# leaf_ard_rev_A.net
KiCad netlist of a schematic drawn in EAGLE
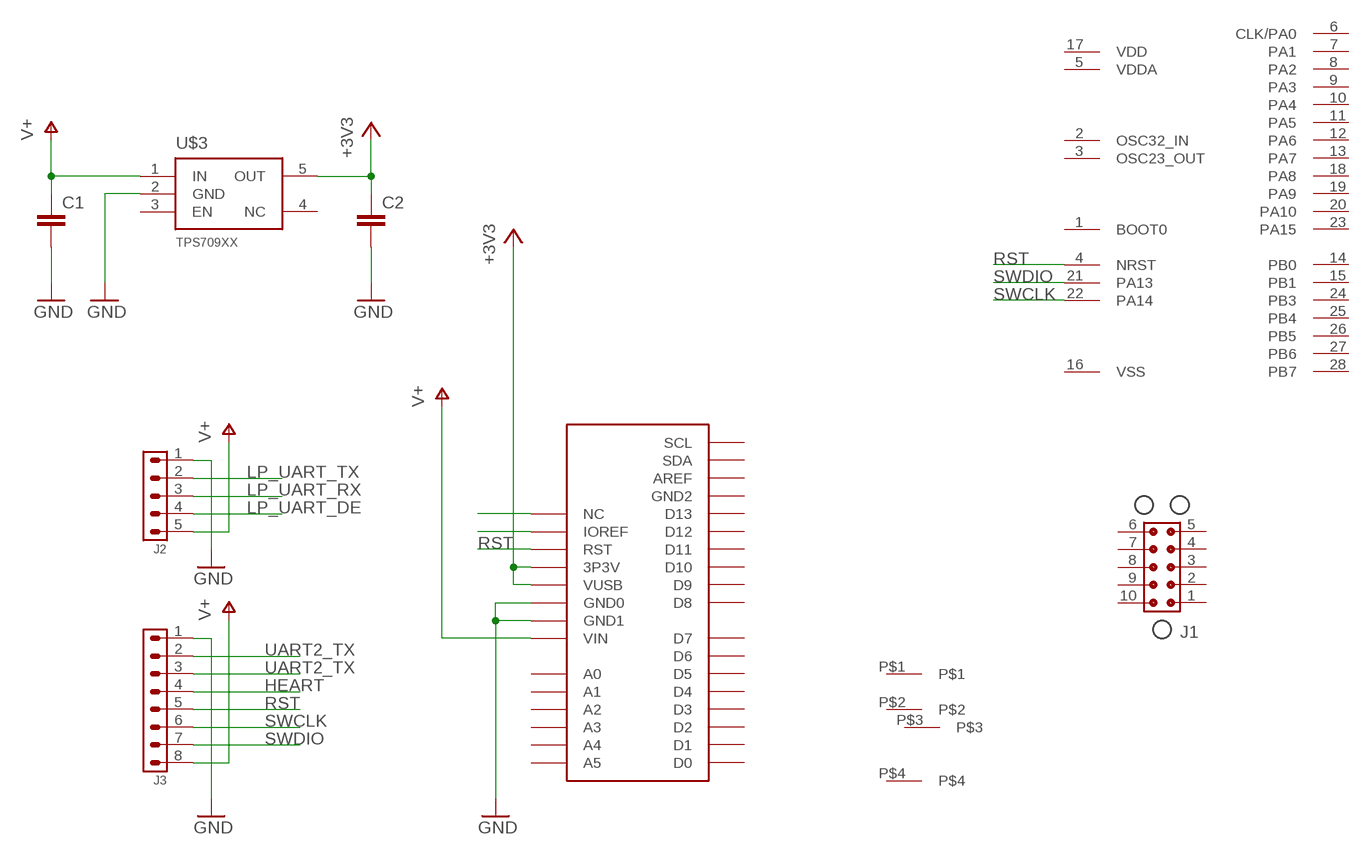
[diagram p0: schematic, sheet 1]

(export (version "E")
  (design (tool "Eeschema 10.0.6"))
  (components
    (comp (ref "C1")
      (value "0603_CAP")
      (footprint "eagle-import:0603")
      (libsource (lib "eagle-import") (part "0603_CAP"))
    )
    (comp (ref "C2")
      (value "0603_CAP")
      (footprint "eagle-import:0603")
      (libsource (lib "eagle-import") (part "0603_CAP"))
    )
    (comp (ref "J1")
      (value "TC_2050_IDC_NL_TOP")
      (footprint "eagle-import:TC_2050_IDC_NL_TOP")
      (libsource (lib "eagle-import") (part "TC_2050_IDC_NL_TOP"))
    )
    (comp (ref "J2")
      (value "CONN_5X1_JST_PA")
      (footprint "eagle-import:CONN_5X1_JST_PA")
      (libsource (lib "eagle-import") (part "CONN_5X1_JST_PA"))
    )
    (comp (ref "J3")
      (value "CONN_8X1_JST_PA")
      (footprint "eagle-import:CONN_8X1_JST_PA")
      (libsource (lib "eagle-import") (part "CONN_8X1_JST_PA"))
    )
    (comp (ref "U$1")
      (value "ARDUINO_UNO_R3")
      (footprint "eagle-import:ARDUINO_UNO_R3")
      (libsource (lib "eagle-import") (part "ARDUINO_UNO_R3"))
    )
    (comp (ref "U$2")
      (value "BMI-S-103")
      (footprint "eagle-import:BMI-S-103")
      (libsource (lib "eagle-import") (part "BMI-S-103"))
    )
    (comp (ref "U$3")
      (value "TPS709XX")
      (footprint "eagle-import:SOT23-5")
      (libsource (lib "eagle-import") (part "TPS709XX"))
    )
    (comp (ref "U1")
      (value "STM32L031G6U6")
      (footprint "eagle-import:STM32_QFN_28_4X4")
      (libsource (lib "eagle-import") (part "STM32L031G6U6"))
    )
  )
  (nets
    (net (code "1") (name "+3V3") (class "Default")
      (node (ref "C2") (pin "P$1") (pinfunction "1_P$1") (pintype "passive"))
      (node (ref "U$1") (pin "P03") (pinfunction "3P3V_P03") (pintype "bidirectional"))
      (node (ref "U$1") (pin "P04") (pinfunction "VUSB_P04") (pintype "bidirectional"))
      (node (ref "U$3") (pin "5") (pinfunction "OUT_5") (pintype "bidirectional"))
    )
    (net (code "2") (name "/HEART") (class "Default")
      (node (ref "J3") (pin "4") (pinfunction "4_4") (pintype "bidirectional"))
    )
    (net (code "3") (name "/LP_UART_DE") (class "Default")
      (node (ref "J2") (pin "4") (pinfunction "4_4") (pintype "bidirectional"))
    )
    (net (code "4") (name "/LP_UART_RX") (class "Default")
      (node (ref "J2") (pin "3") (pinfunction "3_3") (pintype "bidirectional"))
    )
    (net (code "5") (name "/LP_UART_TX") (class "Default")
      (node (ref "J2") (pin "2") (pinfunction "2_2") (pintype "bidirectional"))
    )
    (net (code "6") (name "/RST") (class "Default")
      (node (ref "J3") (pin "5") (pinfunction "5_5") (pintype "bidirectional"))
      (node (ref "U$1") (pin "P02") (pinfunction "RST_P02") (pintype "bidirectional"))
      (node (ref "U1") (pin "4") (pinfunction "NRST_4") (pintype "bidirectional"))
    )
    (net (code "7") (name "/SWCLK") (class "Default")
      (node (ref "J3") (pin "6") (pinfunction "6_6") (pintype "bidirectional"))
      (node (ref "U$1") (pin "P01") (pinfunction "IOREF_P01") (pintype "bidirectional"))
      (node (ref "U1") (pin "22") (pinfunction "PA14_22") (pintype "bidirectional"))
    )
    (net (code "8") (name "/SWDIO") (class "Default")
      (node (ref "J3") (pin "7") (pinfunction "7_7") (pintype "bidirectional"))
      (node (ref "U$1") (pin "P00") (pinfunction "NC_P00") (pintype "bidirectional"))
      (node (ref "U1") (pin "21") (pinfunction "PA13_21") (pintype "bidirectional"))
    )
    (net (code "9") (name "/UART2_TX") (class "Default")
      (node (ref "J3") (pin "2") (pinfunction "2_2") (pintype "bidirectional"))
      (node (ref "J3") (pin "3") (pinfunction "3_3") (pintype "bidirectional"))
    )
    (net (code "10") (name "GND") (class "Default")
      (node (ref "C1") (pin "P$2") (pinfunction "2_P$2") (pintype "passive"))
      (node (ref "C2") (pin "P$2") (pinfunction "2_P$2") (pintype "passive"))
      (node (ref "J2") (pin "1") (pinfunction "1_1") (pintype "bidirectional"))
      (node (ref "J3") (pin "1") (pinfunction "1_1") (pintype "bidirectional"))
      (node (ref "U$1") (pin "P05") (pinfunction "GND0_P05") (pintype "bidirectional"))
      (node (ref "U$1") (pin "P06") (pinfunction "GND1_P06") (pintype "bidirectional"))
      (node (ref "U$3") (pin "2") (pinfunction "GND_2") (pintype "bidirectional"))
    )
    (net (code "11") (name "V+") (class "Default")
      (node (ref "C1") (pin "P$1") (pinfunction "1_P$1") (pintype "passive"))
      (node (ref "J2") (pin "5") (pinfunction "5_5") (pintype "bidirectional"))
      (node (ref "J3") (pin "8") (pinfunction "8_8") (pintype "bidirectional"))
      (node (ref "U$1") (pin "P07") (pinfunction "VIN_P07") (pintype "bidirectional"))
      (node (ref "U$3") (pin "1") (pinfunction "IN_1") (pintype "bidirectional"))
    )
    (net (code "12") (name "unconnected-(J1-Pad1)") (class "Default")
      (node (ref "J1") (pin "1") (pinfunction "1_1") (pintype "bidirectional"))
    )
    (net (code "13") (name "unconnected-(J1-Pad2)") (class "Default")
      (node (ref "J1") (pin "2") (pinfunction "2_2") (pintype "bidirectional"))
    )
    (net (code "14") (name "unconnected-(J1-Pad3)") (class "Default")
      (node (ref "J1") (pin "3") (pinfunction "3_3") (pintype "bidirectional"))
    )
    (net (code "15") (name "unconnected-(J1-Pad4)") (class "Default")
      (node (ref "J1") (pin "4") (pinfunction "4_4") (pintype "bidirectional"))
    )
    (net (code "16") (name "unconnected-(J1-Pad5)") (class "Default")
      (node (ref "J1") (pin "5") (pinfunction "5_5") (pintype "bidirectional"))
    )
    (net (code "17") (name "unconnected-(J1-Pad6)") (class "Default")
      (node (ref "J1") (pin "6") (pinfunction "6_6") (pintype "bidirectional"))
    )
    (net (code "18") (name "unconnected-(J1-Pad7)") (class "Default")
      (node (ref "J1") (pin "7") (pinfunction "7_7") (pintype "bidirectional"))
    )
    (net (code "19") (name "unconnected-(J1-Pad8)") (class "Default")
      (node (ref "J1") (pin "8") (pinfunction "8_8") (pintype "bidirectional"))
    )
    (net (code "20") (name "unconnected-(J1-Pad9)") (class "Default")
      (node (ref "J1") (pin "9") (pinfunction "9_9") (pintype "bidirectional"))
    )
    (net (code "21") (name "unconnected-(J1-Pad10)") (class "Default")
      (node (ref "J1") (pin "10") (pinfunction "10_10") (pintype "bidirectional"))
    )
    (net (code "22") (name "unconnected-(U$1-A0-PadP10)") (class "Default")
      (node (ref "U$1") (pin "P10") (pinfunction "A0_P10") (pintype "bidirectional"))
    )
    (net (code "23") (name "unconnected-(U$1-A1-PadP11)") (class "Default")
      (node (ref "U$1") (pin "P11") (pinfunction "A1_P11") (pintype "bidirectional"))
    )
    (net (code "24") (name "unconnected-(U$1-A2-PadP12)") (class "Default")
      (node (ref "U$1") (pin "P12") (pinfunction "A2_P12") (pintype "bidirectional"))
    )
    (net (code "25") (name "unconnected-(U$1-A3-PadP13)") (class "Default")
      (node (ref "U$1") (pin "P13") (pinfunction "A3_P13") (pintype "bidirectional"))
    )
    (net (code "26") (name "unconnected-(U$1-A4-PadP14)") (class "Default")
      (node (ref "U$1") (pin "P14") (pinfunction "A4_P14") (pintype "bidirectional"))
    )
    (net (code "27") (name "unconnected-(U$1-A5-PadP15)") (class "Default")
      (node (ref "U$1") (pin "P15") (pinfunction "A5_P15") (pintype "bidirectional"))
    )
    (net (code "28") (name "unconnected-(U$1-AREF-PadP37)") (class "Default")
      (node (ref "U$1") (pin "P37") (pinfunction "AREF_P37") (pintype "bidirectional"))
    )
    (net (code "29") (name "unconnected-(U$1-D0-PadP20)") (class "Default")
      (node (ref "U$1") (pin "P20") (pinfunction "D0_P20") (pintype "bidirectional"))
    )
    (net (code "30") (name "unconnected-(U$1-D1-PadP21)") (class "Default")
      (node (ref "U$1") (pin "P21") (pinfunction "D1_P21") (pintype "bidirectional"))
    )
    (net (code "31") (name "unconnected-(U$1-D2-PadP22)") (class "Default")
      (node (ref "U$1") (pin "P22") (pinfunction "D2_P22") (pintype "bidirectional"))
    )
    (net (code "32") (name "unconnected-(U$1-D3-PadP23)") (class "Default")
      (node (ref "U$1") (pin "P23") (pinfunction "D3_P23") (pintype "bidirectional"))
    )
    (net (code "33") (name "unconnected-(U$1-D4-PadP24)") (class "Default")
      (node (ref "U$1") (pin "P24") (pinfunction "D4_P24") (pintype "bidirectional"))
    )
    (net (code "34") (name "unconnected-(U$1-D5-PadP25)") (class "Default")
      (node (ref "U$1") (pin "P25") (pinfunction "D5_P25") (pintype "bidirectional"))
    )
    (net (code "35") (name "unconnected-(U$1-D6-PadP26)") (class "Default")
      (node (ref "U$1") (pin "P26") (pinfunction "D6_P26") (pintype "bidirectional"))
    )
    (net (code "36") (name "unconnected-(U$1-D7-PadP27)") (class "Default")
      (node (ref "U$1") (pin "P27") (pinfunction "D7_P27") (pintype "bidirectional"))
    )
    (net (code "37") (name "unconnected-(U$1-D8-PadP30)") (class "Default")
      (node (ref "U$1") (pin "P30") (pinfunction "D8_P30") (pintype "bidirectional"))
    )
    (net (code "38") (name "unconnected-(U$1-D9-PadP31)") (class "Default")
      (node (ref "U$1") (pin "P31") (pinfunction "D9_P31") (pintype "bidirectional"))
    )
    (net (code "39") (name "unconnected-(U$1-D10-PadP32)") (class "Default")
      (node (ref "U$1") (pin "P32") (pinfunction "D10_P32") (pintype "bidirectional"))
    )
    (net (code "40") (name "unconnected-(U$1-D11-PadP33)") (class "Default")
      (node (ref "U$1") (pin "P33") (pinfunction "D11_P33") (pintype "bidirectional"))
    )
    (net (code "41") (name "unconnected-(U$1-D12-PadP34)") (class "Default")
      (node (ref "U$1") (pin "P34") (pinfunction "D12_P34") (pintype "bidirectional"))
    )
    (net (code "42") (name "unconnected-(U$1-D13-PadP35)") (class "Default")
      (node (ref "U$1") (pin "P35") (pinfunction "D13_P35") (pintype "bidirectional"))
    )
    (net (code "43") (name "unconnected-(U$1-GND2-PadP36)") (class "Default")
      (node (ref "U$1") (pin "P36") (pinfunction "GND2_P36") (pintype "bidirectional"))
    )
    (net (code "44") (name "unconnected-(U$1-SCL-PadP39)") (class "Default")
      (node (ref "U$1") (pin "P39") (pinfunction "SCL_P39") (pintype "bidirectional"))
    )
    (net (code "45") (name "unconnected-(U$1-SDA-PadP38)") (class "Default")
      (node (ref "U$1") (pin "P38") (pinfunction "SDA_P38") (pintype "bidirectional"))
    )
    (net (code "46") (name "unconnected-(U$2-PadP$1)") (class "Default")
      (node (ref "U$2") (pin "P$1") (pinfunction "P$1_P$1") (pintype "bidirectional"))
    )
    (net (code "47") (name "unconnected-(U$2-PadP$2)") (class "Default")
      (node (ref "U$2") (pin "P$2") (pinfunction "P$2_P$2") (pintype "bidirectional"))
    )
    (net (code "48") (name "unconnected-(U$2-PadP$3)") (class "Default")
      (node (ref "U$2") (pin "P$3") (pinfunction "P$3_P$3") (pintype "bidirectional"))
    )
    (net (code "49") (name "unconnected-(U$2-PadP$4)") (class "Default")
      (node (ref "U$2") (pin "P$4") (pinfunction "P$4_P$4") (pintype "bidirectional"))
    )
    (net (code "50") (name "unconnected-(U$3-EN-Pad3)") (class "Default")
      (node (ref "U$3") (pin "3") (pinfunction "EN_3") (pintype "bidirectional"))
    )
    (net (code "51") (name "unconnected-(U$3-NC-Pad4)") (class "Default")
      (node (ref "U$3") (pin "4") (pinfunction "NC_4") (pintype "bidirectional"))
    )
    (net (code "52") (name "unconnected-(U1-BOOT0-Pad1)") (class "Default")
      (node (ref "U1") (pin "1") (pinfunction "BOOT0_1") (pintype "bidirectional"))
    )
    (net (code "53") (name "unconnected-(U1-CLK{slash}PA0-Pad6)") (class "Default")
      (node (ref "U1") (pin "6") (pinfunction "CLK/PA0_6") (pintype "bidirectional"))
    )
    (net (code "54") (name "unconnected-(U1-OSC23_OUT-Pad3)") (class "Default")
      (node (ref "U1") (pin "3") (pinfunction "OSC23_OUT_3") (pintype "bidirectional"))
    )
    (net (code "55") (name "unconnected-(U1-OSC32_IN-Pad2)") (class "Default")
      (node (ref "U1") (pin "2") (pinfunction "OSC32_IN_2") (pintype "bidirectional"))
    )
    (net (code "56") (name "unconnected-(U1-PA1-Pad7)") (class "Default")
      (node (ref "U1") (pin "7") (pinfunction "PA1_7") (pintype "bidirectional"))
    )
    (net (code "57") (name "unconnected-(U1-PA2-Pad8)") (class "Default")
      (node (ref "U1") (pin "8") (pinfunction "PA2_8") (pintype "bidirectional"))
    )
    (net (code "58") (name "unconnected-(U1-PA3-Pad9)") (class "Default")
      (node (ref "U1") (pin "9") (pinfunction "PA3_9") (pintype "bidirectional"))
    )
    (net (code "59") (name "unconnected-(U1-PA4-Pad10)") (class "Default")
      (node (ref "U1") (pin "10") (pinfunction "PA4_10") (pintype "bidirectional"))
    )
    (net (code "60") (name "unconnected-(U1-PA5-Pad11)") (class "Default")
      (node (ref "U1") (pin "11") (pinfunction "PA5_11") (pintype "bidirectional"))
    )
    (net (code "61") (name "unconnected-(U1-PA6-Pad12)") (class "Default")
      (node (ref "U1") (pin "12") (pinfunction "PA6_12") (pintype "bidirectional"))
    )
    (net (code "62") (name "unconnected-(U1-PA7-Pad13)") (class "Default")
      (node (ref "U1") (pin "13") (pinfunction "PA7_13") (pintype "bidirectional"))
    )
    (net (code "63") (name "unconnected-(U1-PA8-Pad18)") (class "Default")
      (node (ref "U1") (pin "18") (pinfunction "PA8_18") (pintype "bidirectional"))
    )
    (net (code "64") (name "unconnected-(U1-PA9-Pad19)") (class "Default")
      (node (ref "U1") (pin "19") (pinfunction "PA9_19") (pintype "bidirectional"))
    )
    (net (code "65") (name "unconnected-(U1-PA10-Pad20)") (class "Default")
      (node (ref "U1") (pin "20") (pinfunction "PA10_20") (pintype "bidirectional"))
    )
    (net (code "66") (name "unconnected-(U1-PA15-Pad23)") (class "Default")
      (node (ref "U1") (pin "23") (pinfunction "PA15_23") (pintype "bidirectional"))
    )
    (net (code "67") (name "unconnected-(U1-PB0-Pad14)") (class "Default")
      (node (ref "U1") (pin "14") (pinfunction "PB0_14") (pintype "bidirectional"))
    )
    (net (code "68") (name "unconnected-(U1-PB1-Pad15)") (class "Default")
      (node (ref "U1") (pin "15") (pinfunction "PB1_15") (pintype "bidirectional"))
    )
    (net (code "69") (name "unconnected-(U1-PB3-Pad24)") (class "Default")
      (node (ref "U1") (pin "24") (pinfunction "PB3_24") (pintype "bidirectional"))
    )
    (net (code "70") (name "unconnected-(U1-PB4-Pad25)") (class "Default")
      (node (ref "U1") (pin "25") (pinfunction "PB4_25") (pintype "bidirectional"))
    )
    (net (code "71") (name "unconnected-(U1-PB5-Pad26)") (class "Default")
      (node (ref "U1") (pin "26") (pinfunction "PB5_26") (pintype "bidirectional"))
    )
    (net (code "72") (name "unconnected-(U1-PB6-Pad27)") (class "Default")
      (node (ref "U1") (pin "27") (pinfunction "PB6_27") (pintype "bidirectional"))
    )
    (net (code "73") (name "unconnected-(U1-PB7-Pad28)") (class "Default")
      (node (ref "U1") (pin "28") (pinfunction "PB7_28") (pintype "bidirectional"))
    )
    (net (code "74") (name "unconnected-(U1-VDD-Pad17)") (class "Default")
      (node (ref "U1") (pin "17") (pinfunction "VDD_17") (pintype "bidirectional"))
    )
    (net (code "75") (name "unconnected-(U1-VDDA-Pad5)") (class "Default")
      (node (ref "U1") (pin "5") (pinfunction "VDDA_5") (pintype "bidirectional"))
    )
    (net (code "76") (name "unconnected-(U1-VSS-Pad16)") (class "Default")
      (node (ref "U1") (pin "16") (pinfunction "VSS_16") (pintype "bidirectional"))
    )
  )
)
